# schematic.net
KiCad netlist of a schematic drawn in EasyEDA
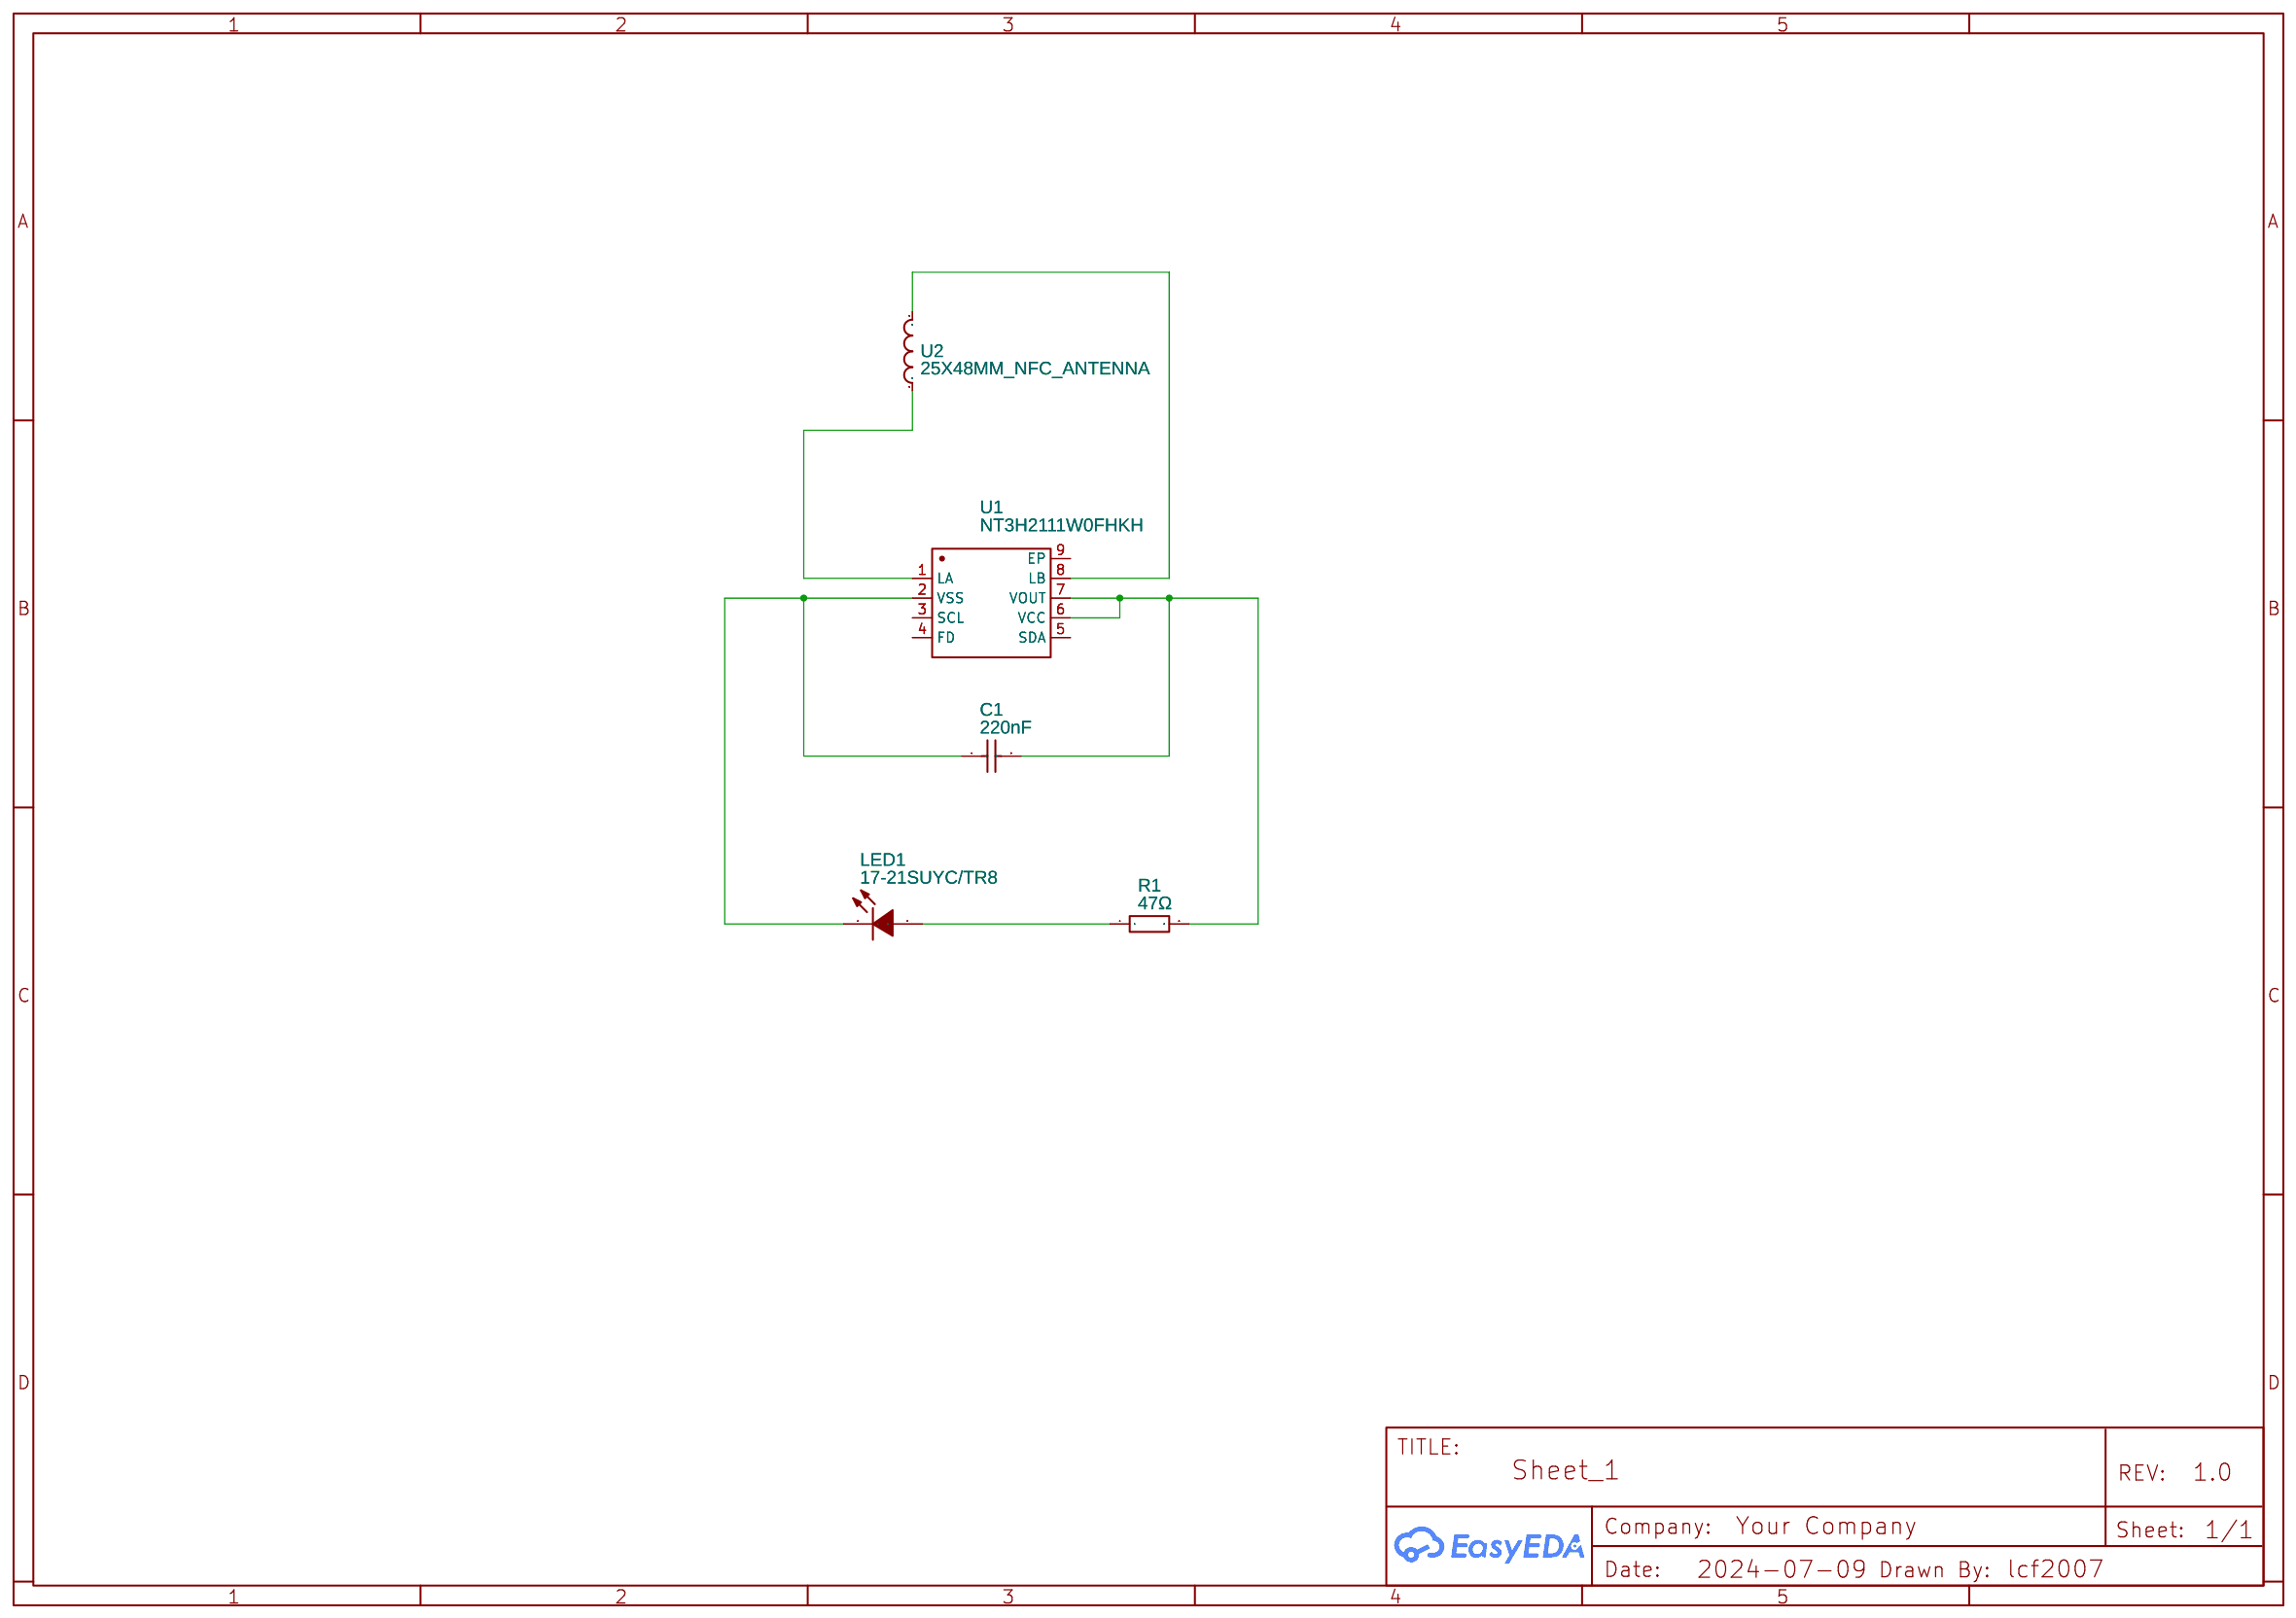
[diagram p0: schematic sheet]

(export (version "E")
  (design (tool "Eeschema 10.0.6"))
  (components
    (comp (ref "C1")
      (value "220nF")
      (fields
        (field (name "Manufacturer Part") "CL10B224KA8NNNC")
        (field (name "Manufacturer") "SAMSUNG(三星)")
      )
      (libsource (lib "") (part "CL10B224KA8NNNC"))
    )
    (comp (ref "LED1")
      (value "17-21SUYC/TR8")
      (fields (field (name "Manufacturer Part") "KT-0805黄灯") (field (name "Manufacturer") "KENTO"))
      (libsource (lib "") (part "17-21SUYC/TR8"))
    )
    (comp (ref "R1")
      (value "47Ω")
      (fields
        (field (name "Manufacturer Part") "0603WAF470JT5E")
        (field (name "Manufacturer") "UNI-ROYAL(厚声)")
      )
      (libsource (lib "") (part "0603WAF470JT5E"))
    )
    (comp (ref "U1")
      (value "NT3H2111W0FHKH")
      (fields (field (name "Manufacturer") "NXP(恩智浦)"))
      (libsource (lib "") (part "NT3H2111W0FHKH"))
    )
    (comp (ref "U2") (value "25X48MM_NFC_ANTENNA") (libsource (lib "") (part "25X48MM_NFC_ANTENNA")))
  )
  (nets
    (net (code "1") (name "Net-(LED1-+)") (class "Default")
      (node (ref "LED1") (pin "1") (pinfunction "+_1") (pintype "unspecified"))
      (node (ref "R1") (pin "1") (pinfunction "1_1") (pintype "input"))
    )
    (net (code "2") (name "Net-(LED1--)") (class "Default")
      (node (ref "C1") (pin "1") (pinfunction "1_1") (pintype "input"))
      (node (ref "LED1") (pin "2") (pinfunction "-_2") (pintype "unspecified"))
      (node (ref "U1") (pin "2") (pinfunction "VSS_2") (pintype "unspecified"))
    )
    (net (code "3") (name "Net-(U1-LA)") (class "Default")
      (node (ref "U1") (pin "1") (pinfunction "LA_1") (pintype "unspecified"))
      (node (ref "U2") (pin "1") (pinfunction "1_1") (pintype "unspecified"))
    )
    (net (code "4") (name "Net-(U1-LB)") (class "Default")
      (node (ref "U1") (pin "8") (pinfunction "LB_8") (pintype "unspecified"))
      (node (ref "U2") (pin "2") (pinfunction "2_2") (pintype "unspecified"))
    )
    (net (code "5") (name "Net-(U1-VCC)") (class "Default")
      (node (ref "C1") (pin "2") (pinfunction "2_2") (pintype "input"))
      (node (ref "R1") (pin "2") (pinfunction "2_2") (pintype "input"))
      (node (ref "U1") (pin "6") (pinfunction "VCC_6") (pintype "unspecified"))
      (node (ref "U1") (pin "7") (pinfunction "VOUT_7") (pintype "unspecified"))
    )
    (net (code "6") (name "unconnected-(U1-EP-Pad9)") (class "Default")
      (node (ref "U1") (pin "9") (pinfunction "EP_9") (pintype "unspecified"))
    )
    (net (code "7") (name "unconnected-(U1-FD-Pad4)") (class "Default")
      (node (ref "U1") (pin "4") (pinfunction "FD_4") (pintype "unspecified"))
    )
    (net (code "8") (name "unconnected-(U1-SCL-Pad3)") (class "Default")
      (node (ref "U1") (pin "3") (pinfunction "SCL_3") (pintype "unspecified"))
    )
    (net (code "9") (name "unconnected-(U1-SDA-Pad5)") (class "Default")
      (node (ref "U1") (pin "5") (pinfunction "SDA_5") (pintype "unspecified"))
    )
  )
)
